# BluetoothAdapter1_0.net
KiCad netlist of a schematic drawn in Altium Designer
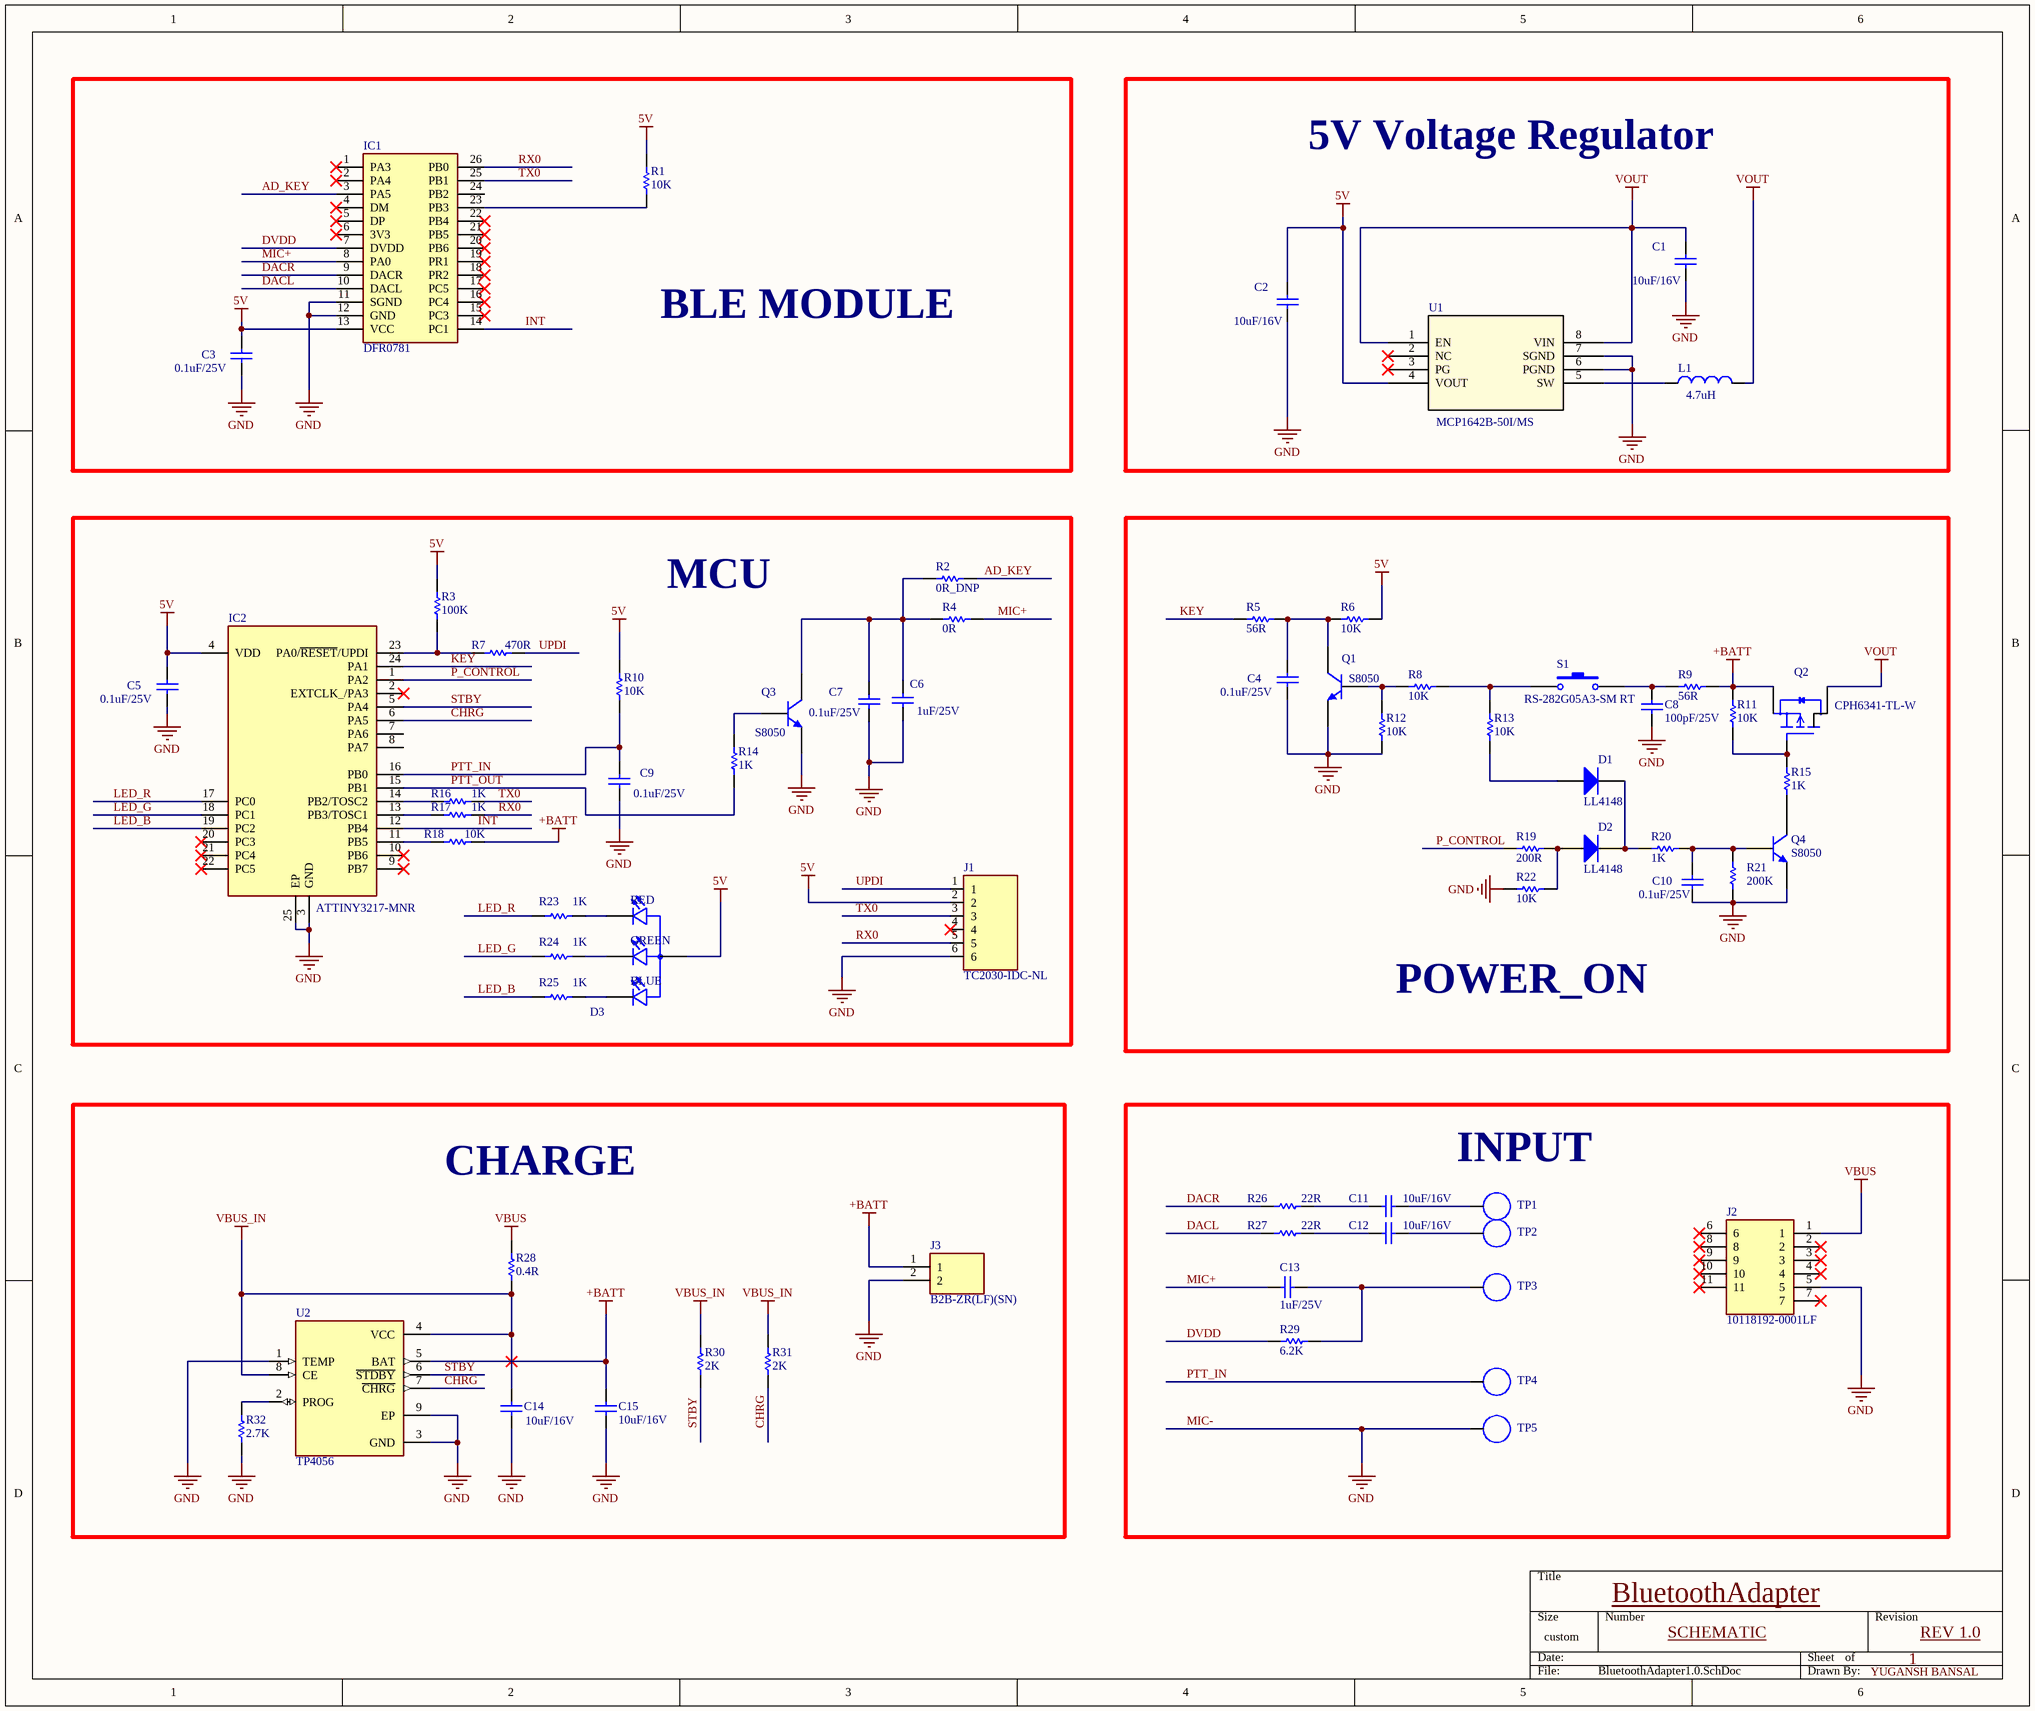
[diagram p0: BluetoothAdapter1.0.SchDoc]

(export (version "E")
  (design (tool "Eeschema 10.0.6"))
  (components
    (comp (ref "C1")
      (value "10uF/16V")
      (footprint "BluetoothAdapter:C0603S")
      (description "10 µF ±20% 16V Ceramic Capacitor X5R 0603 (1608 Metric)")
      (fields
        (field (name "MANUFACTURER") "Murata Electronics")
        (field (name "DIGI-KEY PART NUMBER") "490-10729-6-ND")
      )
      (libsource (lib "myLib") (part "Cap"))
    )
    (comp (ref "C2")
      (value "10uF/16V")
      (footprint "BluetoothAdapter:C0603S")
      (description "10 µF ±20% 16V Ceramic Capacitor X5R 0603 (1608 Metric)")
      (fields
        (field (name "MANUFACTURER") "Murata Electronics")
        (field (name "DIGI-KEY PART NUMBER") "490-10729-6-ND")
      )
      (libsource (lib "myLib") (part "Cap"))
    )
    (comp (ref "C3")
      (value "0.1uF/25V")
      (footprint "BluetoothAdapter:C0603S")
      (description "0.1 µF ±10% 25V Ceramic Capacitor X7R 0603 (1608 Metric)")
      (fields
        (field (name "MANUFACTURER") "KEMET")
        (field (name "DIGI-KEY PART NUMBER") "399-C0603C104K3RAC7867TR-ND")
      )
      (libsource (lib "myLib") (part "Cap"))
    )
    (comp (ref "C4")
      (value "0.1uF/25V")
      (footprint "BluetoothAdapter:C0603S")
      (description "0.1 µF ±10% 25V Ceramic Capacitor X7R 0603 (1608 Metric)")
      (fields
        (field (name "MANUFACTURER") "KEMET")
        (field (name "DIGI-KEY PART NUMBER") "399-C0603C104K3RAC7867TR-ND")
      )
      (libsource (lib "myLib") (part "Cap"))
    )
    (comp (ref "C5")
      (value "0.1uF/25V")
      (footprint "BluetoothAdapter:C0603S")
      (description "0.1 µF ±10% 25V Ceramic Capacitor X7R 0603 (1608 Metric)")
      (fields
        (field (name "MANUFACTURER") "KEMET")
        (field (name "DIGI-KEY PART NUMBER") "399-C0603C104K3RAC7867TR-ND")
      )
      (libsource (lib "myLib") (part "Cap"))
    )
    (comp (ref "C6")
      (value "1uF/25V")
      (footprint "BluetoothAdapter:C0603S")
      (description "1 µF ±10% 25V Ceramic Capacitor X7R 0603 (1608 Metric)")
      (fields
        (field (name "MANUFACTURER") "KEMET")
        (field (name "DIGI-KEY PART NUMBER") "399-C0603C105K3RAC7867DKR-ND")
      )
      (libsource (lib "myLib") (part "Cap"))
    )
    (comp (ref "C7")
      (value "0.1uF/25V")
      (footprint "BluetoothAdapter:C0603S")
      (description "0.1 µF ±10% 25V Ceramic Capacitor X7R 0603 (1608 Metric)")
      (fields
        (field (name "MANUFACTURER") "KEMET")
        (field (name "DIGI-KEY PART NUMBER") "399-C0603C104K3RAC7867TR-ND")
      )
      (libsource (lib "myLib") (part "Cap"))
    )
    (comp (ref "C8")
      (value "100pF/25V")
      (footprint "BluetoothAdapter:C0603S")
      (description "0.1 µF ±10% 25V Ceramic Capacitor X7R 0603 (1608 Metric)")
      (fields
        (field (name "MANUFACTURER") "KEMET")
        (field (name "DIGI-KEY PART NUMBER") "399-C0603C101K3RACAUTODKR-ND")
      )
      (libsource (lib "myLib") (part "Cap"))
    )
    (comp (ref "C9")
      (value "0.1uF/25V")
      (footprint "BluetoothAdapter:C0603S")
      (description "0.1 µF ±10% 25V Ceramic Capacitor X7R 0603 (1608 Metric)")
      (fields
        (field (name "MANUFACTURER") "KEMET")
        (field (name "DIGI-KEY PART NUMBER") "399-C0603C104K3RAC7867TR-ND")
      )
      (libsource (lib "myLib") (part "Cap"))
    )
    (comp (ref "C10")
      (value "0.1uF/25V")
      (footprint "BluetoothAdapter:C0603S")
      (description "0.1 µF ±10% 25V Ceramic Capacitor X7R 0603 (1608 Metric)")
      (fields
        (field (name "MANUFACTURER") "KEMET")
        (field (name "DIGI-KEY PART NUMBER") "399-C0603C104K3RAC7867TR-ND")
      )
      (libsource (lib "myLib") (part "Cap"))
    )
    (comp (ref "C11")
      (value "10uF/16V")
      (footprint "BluetoothAdapter:C0603S")
      (description "10 µF ±20% 16V Ceramic Capacitor X5R 0603 (1608 Metric)")
      (fields
        (field (name "MANUFACTURER") "Murata Electronics")
        (field (name "DIGI-KEY PART NUMBER") "490-10729-6-ND")
      )
      (libsource (lib "myLib") (part "Cap"))
    )
    (comp (ref "C12")
      (value "10uF/16V")
      (footprint "BluetoothAdapter:C0603S")
      (description "10 µF ±20% 16V Ceramic Capacitor X5R 0603 (1608 Metric)")
      (fields
        (field (name "MANUFACTURER") "Murata Electronics")
        (field (name "DIGI-KEY PART NUMBER") "490-10729-6-ND")
      )
      (libsource (lib "myLib") (part "Cap"))
    )
    (comp (ref "C13")
      (value "1uF/25V")
      (footprint "BluetoothAdapter:C0603S")
      (description "1 µF ±10% 25V Ceramic Capacitor X7R 0603 (1608 Metric)")
      (fields
        (field (name "MANUFACTURER") "KEMET")
        (field (name "DIGI-KEY PART NUMBER") "399-C0603C105K3RAC7867DKR-ND")
      )
      (libsource (lib "myLib") (part "Cap"))
    )
    (comp (ref "C14")
      (value "10uF/16V")
      (footprint "BluetoothAdapter:C0603S")
      (description "10 µF ±20% 16V Ceramic Capacitor X5R 0603 (1608 Metric)")
      (fields
        (field (name "MANUFACTURER") "Murata Electronics")
        (field (name "DIGI-KEY PART NUMBER") "490-10729-6-ND")
      )
      (libsource (lib "myLib") (part "Cap"))
    )
    (comp (ref "C15")
      (value "10uF/16V")
      (footprint "BluetoothAdapter:C0603S")
      (description "10 µF ±20% 16V Ceramic Capacitor X5R 0603 (1608 Metric)")
      (fields
        (field (name "MANUFACTURER") "Murata Electronics")
        (field (name "DIGI-KEY PART NUMBER") "490-10729-6-ND")
      )
      (libsource (lib "myLib") (part "Cap"))
    )
    (comp (ref "D1")
      (value "LL4148")
      (footprint "DIO_LL4148")
      (description "Diode Standard 100 V 200mA Surface Mount SOD-80")
      (fields (field (name "MANUFACTURER") "onsemi") (field (name "DIGI-KEY PART NUMBER") "LL4148FSCT-ND"))
      (libsource (lib "Miscellaneous Devices") (part "Diode"))
    )
    (comp (ref "D2")
      (value "LL4148")
      (footprint "DIO_LL4148")
      (description "Diode Standard 100 V 200mA Surface Mount SOD-80")
      (fields (field (name "MANUFACTURER") "onsemi") (field (name "DIGI-KEY PART NUMBER") "LL4148FSCT-ND"))
      (libsource (lib "Miscellaneous Devices") (part "Diode"))
    )
    (comp (ref "D3")
      (value "LED RGB MIXED WHITE ( 1.6(L)X1.6")
      (footprint "BluetoothAdapter:LED_B38G3RGB-10D0003H2U1930")
      (description "Red, Green, Blue (RGB) LED Indication - Discrete 2V Red, 3V Green, 3V Blue 0606 (1616 Metric)")
      (fields
        (field (name "MANUFACTURER") "Harvatek Corporation")
        (field (name "DIGI-KEY PART NUMBER") "3147-B38G3RGB-10D0003H2U1930DKR-ND")
      )
      (libsource (lib "BluetoothAdapter") (part "B38G3RGB-10D0003H2U1930"))
    )
    (comp (ref "IC1")
      (value "DFR0781")
      (footprint "BluetoothAdapter:DFR0781")
      (description "Bluetooth Bluetooth v5.0 Transceiver Module Antenna Not Included Surface Mount")
      (fields (field (name "MANUFACTURER") "DFRobot") (field (name "DIGI-KEY PART NUMBER") "1738-DFR0781-ND"))
      (libsource (lib "BluetoothAdapter") (part "DFR0781"))
    )
    (comp (ref "IC2")
      (value "ATTINY3217-MNR")
      (footprint "BluetoothAdapter:QFN50P400X400X90-25N-D")
      (fields
        (field (name "MANUFACTURER") "Microchip")
        (field (name "DIGI-KEY PART NUMBER") "ATTINY3217-MNRDKR-ND")
        (field (name "Comment") "IC MCU 8BIT 32KB FLASH 24VQFN")
      )
      (libsource (lib "BluetoothAdapter") (part "ATTINY3217-MNR"))
    )
    (comp (ref "J1")
      (value "TC2030-IDC-NL")
      (footprint "BluetoothAdapter:TAG_TC2030-IDC-NL")
      (description "6-PIN PLUG-OF-NAILS CABLE 6")
      (fields (field (name "MF") "Tag-Connect"))
      (libsource (lib "BluetoothAdapter") (part "TC2030-IDC-NL"))
    )
    (comp (ref "J2")
      (value "10118192-0001LF")
      (footprint "BluetoothAdapter:101181920001LF")
      (description "USB - micro B USB 2.0 Receptacle Connector 5 Position Surface Mount, Right Angle")
      (fields (field (name "MANUFACTURER") "Amphenol") (field (name "DIGI-KEY PART NUMBER") "609-4613-6-ND"))
      (libsource (lib "BluetoothAdapter") (part "10118192-0001LF"))
    )
    (comp (ref "J3")
      (value "B2B-ZR(LF)(SN)")
      (footprint "BluetoothAdapter:SHDR2W50P0X150_1X2_450X350X450P")
      (description "Connector Header Through Hole 2 position 0.059\" (1.50mm)")
      (fields
        (field (name "MANUFACTURER") "JST (JAPAN SOLDERLESS TERMINALS)")
        (field (name "DIGI-KEY PART NUMBER") "455-1657-ND")
      )
      (libsource (lib "BluetoothAdapter") (part "B2B-ZR(LF)(SN)"))
    )
    (comp (ref "L1")
      (value "4.7uH")
      (footprint "INDC2520X100N:INDC2520X100N")
      (description "4.7 µH Shielded Multilayer Inductor 1.3 A 120mOhm 1008 (2520 Metric)")
      (fields
        (field (name "MANUFACTURER") "Abracon LLC")
        (field (name "DIGI-KEY PART NUMBER") "535-12797-6-ND")
      )
      (libsource (lib "Blueguard") (part "AIML-1008HC-4R7M-T"))
    )
    (comp (ref "Q1")
      (value "S8050")
      (footprint "BluetoothAdapter:SOT23-3D")
      (description "Bipolar (BJT) Transistor NPN 25 V 500 mA 150MHz 300 mW Surface Mount SOT-23")
      (fields (field (name "MANUFACTURER") "MDD") (field (name "DIGI-KEY PART NUMBER") "3372-S8050TR-ND"))
      (libsource (lib "BluetoothAdapter") (part "S8050"))
    )
    (comp (ref "Q2")
      (value "CPH6341-TL-W")
      (footprint "BluetoothAdapter:SOT95P285X140-6N")
      (description "P-Channel 30 V 5A (Ta) 1.6W (Ta) Surface Mount 6-CPH")
      (fields
        (field (name "MANUFACTURER") "onsemi")
        (field (name "DIGI-KEY PART NUMBER") "CPH6341-TL-WOSDKR-ND")
      )
      (libsource (lib "BluetoothAdapter") (part "CPH6341-TL-W"))
    )
    (comp (ref "Q3")
      (value "S8050")
      (footprint "BluetoothAdapter:SOT23-3D")
      (description "Bipolar (BJT) Transistor NPN 25 V 500 mA 150MHz 300 mW Surface Mount SOT-23")
      (fields (field (name "MANUFACTURER") "MDD") (field (name "DIGI-KEY PART NUMBER") "3372-S8050TR-ND"))
      (libsource (lib "BluetoothAdapter") (part "S8050"))
    )
    (comp (ref "Q4")
      (value "S8050")
      (footprint "BluetoothAdapter:SOT23-3D")
      (description "Bipolar (BJT) Transistor NPN 25 V 500 mA 150MHz 300 mW Surface Mount SOT-23")
      (fields (field (name "MANUFACTURER") "MDD") (field (name "DIGI-KEY PART NUMBER") "3372-S8050TR-ND"))
      (libsource (lib "BluetoothAdapter") (part "S8050"))
    )
    (comp (ref "R1")
      (value "10K")
      (footprint "BluetoothAdapter:R0603S")
      (description "10 kOhms ±1% 0.1W, 1/10W Chip Resistor 0603 (1608 Metric) Moisture Resistant Thick Film")
      (fields (field (name "MANUFACTURER") "YAGEO") (field (name "DIGI-KEY PART NUMBER") "311-10.0KHRCT-ND"))
      (libsource (lib "dif") (part "R0603"))
    )
    (comp (ref "R2")
      (value "0R_DNP")
      (footprint "BluetoothAdapter:R0603S")
      (description "0Ohms ±1% 0.1W, 1/10W Chip Resistor 0603 (1608 Metric) Moisture Resistant Thick Film")
      (fields (field (name "MANUFACTURER") "YAGEO") (field (name "DIGI-KEY PART NUMBER") "311-0.0GRDKR-ND"))
      (libsource (lib "dif") (part "R0603"))
    )
    (comp (ref "R3")
      (value "100K")
      (footprint "BluetoothAdapter:R0603S")
      (description "100 kOhms ±1% 0.1W, 1/10W Chip Resistor 0603 (1608 Metric) Moisture Resistant Thick Film")
      (fields (field (name "MANUFACTURER") "YAGEO") (field (name "DIGI-KEY PART NUMBER") "311-100KHRDKR-ND"))
      (libsource (lib "dif") (part "R0603"))
    )
    (comp (ref "R4")
      (value "0R")
      (footprint "BluetoothAdapter:R0603S")
      (description "0Ohms ±1% 0.1W, 1/10W Chip Resistor 0603 (1608 Metric) Moisture Resistant Thick Film")
      (fields (field (name "MANUFACTURER") "YAGEO") (field (name "DIGI-KEY PART NUMBER") "311-0.0GRDKR-ND"))
      (libsource (lib "dif") (part "R0603"))
    )
    (comp (ref "R5")
      (value "56R")
      (footprint "BluetoothAdapter:R0603S")
      (description "1 kOhms ±1% 0.1W, 1/10W Chip Resistor 0603 (1608 Metric) Moisture Resistant Thick Film")
      (fields (field (name "MANUFACTURER") "YAGEO") (field (name "DIGI-KEY PART NUMBER") "311-56.0HRDKR-ND"))
      (libsource (lib "dif") (part "R0603"))
    )
    (comp (ref "R6")
      (value "10K")
      (footprint "BluetoothAdapter:R0603S")
      (description "10 kOhms ±1% 0.1W, 1/10W Chip Resistor 0603 (1608 Metric) Moisture Resistant Thick Film")
      (fields (field (name "MANUFACTURER") "YAGEO") (field (name "DIGI-KEY PART NUMBER") "311-10.0KHRCT-ND"))
      (libsource (lib "dif") (part "R0603"))
    )
    (comp (ref "R7")
      (value "470R")
      (footprint "BluetoothAdapter:R0603S")
      (description "470 Ohms ±1% 0.1W, 1/10W Chip Resistor 0603 (1608 Metric) Moisture Resistant Thick Film")
      (fields (field (name "MANUFACTURER") "YAGEO") (field (name "DIGI-KEY PART NUMBER") "311-470HRDKR-ND"))
      (libsource (lib "dif") (part "R0603"))
    )
    (comp (ref "R8")
      (value "10K")
      (footprint "BluetoothAdapter:R0603S")
      (description "10 kOhms ±1% 0.1W, 1/10W Chip Resistor 0603 (1608 Metric) Moisture Resistant Thick Film")
      (fields (field (name "MANUFACTURER") "YAGEO") (field (name "DIGI-KEY PART NUMBER") "311-10.0KHRCT-ND"))
      (libsource (lib "dif") (part "R0603"))
    )
    (comp (ref "R9")
      (value "56R")
      (footprint "BluetoothAdapter:R0603S")
      (description "1 kOhms ±1% 0.1W, 1/10W Chip Resistor 0603 (1608 Metric) Moisture Resistant Thick Film")
      (fields (field (name "MANUFACTURER") "YAGEO") (field (name "DIGI-KEY PART NUMBER") "311-56.0HRDKR-ND"))
      (libsource (lib "dif") (part "R0603"))
    )
    (comp (ref "R10")
      (value "10K")
      (footprint "BluetoothAdapter:R0603S")
      (description "10 kOhms ±1% 0.1W, 1/10W Chip Resistor 0603 (1608 Metric) Moisture Resistant Thick Film")
      (fields (field (name "MANUFACTURER") "YAGEO") (field (name "DIGI-KEY PART NUMBER") "311-10.0KHRCT-ND"))
      (libsource (lib "dif") (part "R0603"))
    )
    (comp (ref "R11")
      (value "10K")
      (footprint "BluetoothAdapter:R0603S")
      (description "10 kOhms ±1% 0.1W, 1/10W Chip Resistor 0603 (1608 Metric) Moisture Resistant Thick Film")
      (fields (field (name "MANUFACTURER") "YAGEO") (field (name "DIGI-KEY PART NUMBER") "311-10.0KHRCT-ND"))
      (libsource (lib "dif") (part "R0603"))
    )
    (comp (ref "R12")
      (value "10K")
      (footprint "BluetoothAdapter:R0603S")
      (description "10 kOhms ±1% 0.1W, 1/10W Chip Resistor 0603 (1608 Metric) Moisture Resistant Thick Film")
      (fields (field (name "MANUFACTURER") "YAGEO") (field (name "DIGI-KEY PART NUMBER") "311-10.0KHRCT-ND"))
      (libsource (lib "dif") (part "R0603"))
    )
    (comp (ref "R13")
      (value "10K")
      (footprint "BluetoothAdapter:R0603S")
      (description "10 kOhms ±1% 0.1W, 1/10W Chip Resistor 0603 (1608 Metric) Moisture Resistant Thick Film")
      (fields (field (name "MANUFACTURER") "YAGEO") (field (name "DIGI-KEY PART NUMBER") "311-10.0KHRCT-ND"))
      (libsource (lib "dif") (part "R0603"))
    )
    (comp (ref "R14")
      (value "1K")
      (footprint "BluetoothAdapter:R0603S")
      (description "1 kOhms ±1% 0.1W, 1/10W Chip Resistor 0603 (1608 Metric) Moisture Resistant Thick Film")
      (fields (field (name "MANUFACTURER") "YAGEO") (field (name "DIGI-KEY PART NUMBER") "311-1.00KHRTR-ND"))
      (libsource (lib "dif") (part "R0603"))
    )
    (comp (ref "R15")
      (value "1K")
      (footprint "BluetoothAdapter:R0603S")
      (description "1 kOhms ±1% 0.1W, 1/10W Chip Resistor 0603 (1608 Metric) Moisture Resistant Thick Film")
      (fields (field (name "MANUFACTURER") "YAGEO") (field (name "DIGI-KEY PART NUMBER") "311-1.00KHRTR-ND"))
      (libsource (lib "dif") (part "R0603"))
    )
    (comp (ref "R16")
      (value "1K")
      (footprint "BluetoothAdapter:R0603S")
      (description "1 kOhms ±1% 0.1W, 1/10W Chip Resistor 0603 (1608 Metric) Moisture Resistant Thick Film")
      (fields (field (name "MANUFACTURER") "YAGEO") (field (name "DIGI-KEY PART NUMBER") "311-1.00KHRTR-ND"))
      (libsource (lib "dif") (part "R0603"))
    )
    (comp (ref "R17")
      (value "1K")
      (footprint "BluetoothAdapter:R0603S")
      (description "1 kOhms ±1% 0.1W, 1/10W Chip Resistor 0603 (1608 Metric) Moisture Resistant Thick Film")
      (fields (field (name "MANUFACTURER") "YAGEO") (field (name "DIGI-KEY PART NUMBER") "311-1.00KHRTR-ND"))
      (libsource (lib "dif") (part "R0603"))
    )
    (comp (ref "R18")
      (value "10K")
      (footprint "BluetoothAdapter:R0603S")
      (description "10 kOhms ±1% 0.1W, 1/10W Chip Resistor 0603 (1608 Metric) Moisture Resistant Thick Film")
      (fields (field (name "MANUFACTURER") "YAGEO") (field (name "DIGI-KEY PART NUMBER") "311-10.0KHRCT-ND"))
      (libsource (lib "dif") (part "R0603"))
    )
    (comp (ref "R19")
      (value "200R")
      (footprint "BluetoothAdapter:R0603S")
      (description "10 kOhms ±1% 0.1W, 1/10W Chip Resistor 0603 (1608 Metric) Moisture Resistant Thick Film")
      (fields (field (name "MANUFACTURER") "YAGEO") (field (name "DIGI-KEY PART NUMBER") "311-200HRDKR-ND"))
      (libsource (lib "dif") (part "R0603"))
    )
    (comp (ref "R20")
      (value "1K")
      (footprint "BluetoothAdapter:R0603S")
      (description "1 kOhms ±1% 0.1W, 1/10W Chip Resistor 0603 (1608 Metric) Moisture Resistant Thick Film")
      (fields (field (name "MANUFACTURER") "YAGEO") (field (name "DIGI-KEY PART NUMBER") "311-1.00KHRTR-ND"))
      (libsource (lib "dif") (part "R0603"))
    )
    (comp (ref "R21")
      (value "200K")
      (footprint "BluetoothAdapter:R0603S")
      (description "100 kOhms ±1% 0.1W, 1/10W Chip Resistor 0603 (1608 Metric) Moisture Resistant Thick Film")
      (fields
        (field (name "MANUFACTURER") "YAGEO")
        (field (name "DIGI-KEY PART NUMBER") "13-RC0603FR-10200KLDKR-ND")
      )
      (libsource (lib "dif") (part "R0603"))
    )
    (comp (ref "R22")
      (value "10K")
      (footprint "BluetoothAdapter:R0603S")
      (description "10 kOhms ±1% 0.1W, 1/10W Chip Resistor 0603 (1608 Metric) Moisture Resistant Thick Film")
      (fields (field (name "MANUFACTURER") "YAGEO") (field (name "DIGI-KEY PART NUMBER") "311-10.0KHRCT-ND"))
      (libsource (lib "dif") (part "R0603"))
    )
    (comp (ref "R23")
      (value "1K")
      (footprint "BluetoothAdapter:R0603S")
      (description "1 kOhms ±1% 0.1W, 1/10W Chip Resistor 0603 (1608 Metric) Moisture Resistant Thick Film")
      (fields (field (name "MANUFACTURER") "YAGEO") (field (name "DIGI-KEY PART NUMBER") "311-1.00KHRTR-ND"))
      (libsource (lib "dif") (part "R0603"))
    )
    (comp (ref "R24")
      (value "1K")
      (footprint "BluetoothAdapter:R0603S")
      (description "1 kOhms ±1% 0.1W, 1/10W Chip Resistor 0603 (1608 Metric) Moisture Resistant Thick Film")
      (fields (field (name "MANUFACTURER") "YAGEO") (field (name "DIGI-KEY PART NUMBER") "311-1.00KHRTR-ND"))
      (libsource (lib "dif") (part "R0603"))
    )
    (comp (ref "R25")
      (value "1K")
      (footprint "BluetoothAdapter:R0603S")
      (description "1 kOhms ±1% 0.1W, 1/10W Chip Resistor 0603 (1608 Metric) Moisture Resistant Thick Film")
      (fields (field (name "MANUFACTURER") "YAGEO") (field (name "DIGI-KEY PART NUMBER") "311-1.00KHRTR-ND"))
      (libsource (lib "dif") (part "R0603"))
    )
    (comp (ref "R26")
      (value "22R")
      (footprint "BluetoothAdapter:R0603S")
      (description "22 Ohms ±5% 0.1W, 1/10W Chip Resistor 0603 (1608 Metric) Moisture Resistant Thick Film")
      (fields (field (name "MANUFACTURER") "YAGEO") (field (name "DIGI-KEY PART NUMBER") "311-22GRDKR-ND"))
      (libsource (lib "dif") (part "R0603"))
    )
    (comp (ref "R27")
      (value "22R")
      (footprint "BluetoothAdapter:R0603S")
      (description "22 Ohms ±5% 0.1W, 1/10W Chip Resistor 0603 (1608 Metric) Moisture Resistant Thick Film")
      (fields (field (name "MANUFACTURER") "YAGEO") (field (name "DIGI-KEY PART NUMBER") "311-22GRDKR-ND"))
      (libsource (lib "dif") (part "R0603"))
    )
    (comp (ref "R28")
      (value "0.4R")
      (footprint "BluetoothAdapter:R1206S")
      (fields
        (field (name "MANUFACTURER") "YAGEO")
        (field (name "DIGI-KEY PART NUMBER") "311-.4LWDKR-ND")
        (field (name "Comment") "RES 0.4 OHM 1% 1/4W 1206")
      )
      (libsource (lib "dif") (part "R0603"))
    )
    (comp (ref "R29")
      (value "6.2K")
      (footprint "BluetoothAdapter:R0603S")
      (description "6.2 kOhms ±1% 0.1W, 1/10W Chip Resistor 0603 (1608 Metric) Moisture Resistant Thick Film")
      (fields (field (name "MANUFACTURER") "YAGEO") (field (name "DIGI-KEY PART NUMBER") "311-6.20KHRDKR-ND"))
      (libsource (lib "dif") (part "R0603"))
    )
    (comp (ref "R30")
      (value "2K")
      (footprint "BluetoothAdapter:R0603S")
      (description "2 kOhms ±1% 0.1W, 1/10W Chip Resistor 0603 (1608 Metric) Moisture Resistant Thick Film")
      (fields (field (name "MANUFACTURER") "YAGEO") (field (name "DIGI-KEY PART NUMBER") "311-2.00KHRDKR-ND"))
      (libsource (lib "dif") (part "R0603"))
    )
    (comp (ref "R31")
      (value "2K")
      (footprint "BluetoothAdapter:R0603S")
      (description "2 kOhms ±1% 0.1W, 1/10W Chip Resistor 0603 (1608 Metric) Moisture Resistant Thick Film")
      (fields (field (name "MANUFACTURER") "YAGEO") (field (name "DIGI-KEY PART NUMBER") "311-2.00KHRDKR-ND"))
      (libsource (lib "dif") (part "R0603"))
    )
    (comp (ref "R32")
      (value "2.7K")
      (footprint "BluetoothAdapter:R0603S")
      (description "2.7 kOhms ±1% 0.1W, 1/10W Chip Resistor 0603 (1608 Metric) Moisture Resistant Thick Film")
      (fields (field (name "MANUFACTURER") "YAGEO") (field (name "DIGI-KEY PART NUMBER") "311-2.70KHRDKR-ND"))
      (libsource (lib "dif") (part "R0603"))
    )
    (comp (ref "S1")
      (value "RS-282G05A3-SM RT")
      (footprint "BluetoothAdapter:RS282G05A3SMRT")
      (description "Tactile Switch SPST-NO Top Actuated Surface Mount")
      (fields
        (field (name "MANUFACTURER") "C & K COMPONENTS")
        (field (name "DIGI-KEY PART NUMBER") "CKN10384DKR-ND")
      )
      (libsource (lib "BluetoothAdapter") (part "RS282G05A3SMRT"))
    )
    (comp (ref "TP1")
      (value "TP")
      (footprint "BluetoothAdapter:TP")
      (libsource (lib "BluetoothAdapter") (part "TP"))
    )
    (comp (ref "TP2")
      (value "TP")
      (footprint "BluetoothAdapter:TP")
      (libsource (lib "BluetoothAdapter") (part "TP"))
    )
    (comp (ref "TP3")
      (value "TP")
      (footprint "BluetoothAdapter:TP")
      (libsource (lib "BluetoothAdapter") (part "TP"))
    )
    (comp (ref "TP4")
      (value "TP")
      (footprint "BluetoothAdapter:TP")
      (libsource (lib "BluetoothAdapter") (part "TP"))
    )
    (comp (ref "TP5")
      (value "TP")
      (footprint "BluetoothAdapter:TP")
      (libsource (lib "BluetoothAdapter") (part "TP"))
    )
    (comp (ref "U1")
      (value "MCP1642B-50I/MS")
      (footprint "MCP1642B-50:MCP1642B-50I/MS")
      (fields
        (field (name "MANUFACTURER") "Microchip Technology")
        (field (name "DIGI-KEY PART NUMBER") "MCP1642B-50I/MS-ND")
        (field (name "Comment") "IC REG BOOST 5V 800MA 8MSOP")
      )
      (libsource (lib "Blueguard") (part "MCP1642B-50I/MS"))
    )
    (comp (ref "U2")
      (value "TP4056")
      (footprint "BluetoothAdapter:SOP127P600X175-9N")
      (description "Complete single cell Li-Ion battery with a constant current / constant voltage linear charger")
      (fields
        (field (name "MANUFACTURER") "TPOWER semiconductor Co.,LTD.")
        (field (name "DIGI-KEY PART NUMBER") "C382139")
      )
      (libsource (lib "BluetoothAdapter") (part "TP4056"))
    )
  )
  (nets
    (net (code "1") (name "+BATT") (class "Default")
      (node (ref "C15") (pin "2") (pinfunction "2_2") (pintype "passive"))
      (node (ref "J3") (pin "1") (pinfunction "1_1") (pintype "passive"))
      (node (ref "Q2") (pin "4") (pinfunction "S_4") (pintype "passive"))
      (node (ref "R11") (pin "1") (pinfunction "1_1") (pintype "passive"))
      (node (ref "R18") (pin "2") (pinfunction "2_2") (pintype "passive"))
      (node (ref "R9") (pin "2") (pinfunction "2_2") (pintype "passive"))
      (node (ref "U2") (pin "5") (pinfunction "BAT_5") (pintype "output"))
    )
    (net (code "2") (name "/AD_KEY") (class "Default")
      (node (ref "IC1") (pin "3") (pinfunction "PA5_3") (pintype "passive"))
      (node (ref "R2") (pin "1") (pinfunction "1_1") (pintype "passive"))
    )
    (net (code "3") (name "/CHRG") (class "Default")
      (node (ref "IC2") (pin "6") (pinfunction "PA5_6") (pintype "passive"))
      (node (ref "R31") (pin "2") (pinfunction "2_2") (pintype "passive"))
      (node (ref "U2") (pin "7") (pinfunction "~{CHRG}_7") (pintype "output"))
    )
    (net (code "4") (name "/DACL") (class "Default")
      (node (ref "IC1") (pin "10") (pinfunction "DACL_10") (pintype "passive"))
      (node (ref "R27") (pin "1") (pinfunction "1_1") (pintype "passive"))
    )
    (net (code "5") (name "/DACR") (class "Default")
      (node (ref "IC1") (pin "9") (pinfunction "DACR_9") (pintype "passive"))
      (node (ref "R26") (pin "1") (pinfunction "1_1") (pintype "passive"))
    )
    (net (code "6") (name "/DVDD") (class "Default")
      (node (ref "IC1") (pin "7") (pinfunction "DVDD_7") (pintype "passive"))
      (node (ref "R29") (pin "1") (pinfunction "1_1") (pintype "passive"))
    )
    (net (code "7") (name "/INT") (class "Default")
      (node (ref "IC1") (pin "14") (pinfunction "PC1_14") (pintype "passive"))
      (node (ref "IC2") (pin "12") (pinfunction "PB4_12") (pintype "passive"))
    )
    (net (code "8") (name "/KEY") (class "Default")
      (node (ref "IC2") (pin "24") (pinfunction "PA1_24") (pintype "passive"))
      (node (ref "R5") (pin "1") (pinfunction "1_1") (pintype "passive"))
    )
    (net (code "9") (name "/LED_B") (class "Default")
      (node (ref "IC2") (pin "19") (pinfunction "PC2_19") (pintype "passive"))
      (node (ref "R25") (pin "1") (pinfunction "1_1") (pintype "passive"))
    )
    (net (code "10") (name "/LED_G") (class "Default")
      (node (ref "IC2") (pin "18") (pinfunction "PC1_18") (pintype "passive"))
      (node (ref "R24") (pin "1") (pinfunction "1_1") (pintype "passive"))
    )
    (net (code "11") (name "/LED_R") (class "Default")
      (node (ref "IC2") (pin "17") (pinfunction "PC0_17") (pintype "passive"))
      (node (ref "R23") (pin "1") (pinfunction "1_1") (pintype "passive"))
    )
    (net (code "12") (name "/MIC+") (class "Default")
      (node (ref "C13") (pin "1") (pinfunction "1_1") (pintype "passive"))
      (node (ref "IC1") (pin "8") (pinfunction "PA0_8") (pintype "passive"))
      (node (ref "R4") (pin "2") (pinfunction "2_2") (pintype "passive"))
    )
    (net (code "13") (name "/PTT_IN") (class "Default")
      (node (ref "C9") (pin "1") (pinfunction "1_1") (pintype "passive"))
      (node (ref "IC2") (pin "16") (pinfunction "PB0_16") (pintype "passive"))
      (node (ref "R10") (pin "2") (pinfunction "2_2") (pintype "passive"))
      (node (ref "TP4") (pin "1") (pinfunction "1_1") (pintype "passive"))
    )
    (net (code "14") (name "/PTT_OUT") (class "Default")
      (node (ref "IC2") (pin "15") (pinfunction "PB1_15") (pintype "passive"))
      (node (ref "R14") (pin "1") (pinfunction "1_1") (pintype "passive"))
    )
    (net (code "15") (name "/P_CONTROL") (class "Default")
      (node (ref "IC2") (pin "1") (pinfunction "PA2_1") (pintype "passive"))
      (node (ref "R19") (pin "1") (pinfunction "1_1") (pintype "passive"))
    )
    (net (code "16") (name "/RX0") (class "Default")
      (node (ref "IC1") (pin "26") (pinfunction "PB0_26") (pintype "passive"))
      (node (ref "J1") (pin "5") (pinfunction "5_5") (pintype "passive"))
      (node (ref "R17") (pin "2") (pinfunction "2_2") (pintype "passive"))
    )
    (net (code "17") (name "/STBY") (class "Default")
      (node (ref "IC2") (pin "5") (pinfunction "PA4_5") (pintype "passive"))
      (node (ref "R30") (pin "2") (pinfunction "2_2") (pintype "passive"))
      (node (ref "U2") (pin "6") (pinfunction "~{STDBY}_6") (pintype "output"))
    )
    (net (code "18") (name "/TX0") (class "Default")
      (node (ref "IC1") (pin "25") (pinfunction "PB1_25") (pintype "passive"))
      (node (ref "J1") (pin "3") (pinfunction "3_3") (pintype "passive"))
      (node (ref "R16") (pin "2") (pinfunction "2_2") (pintype "passive"))
    )
    (net (code "19") (name "/UPDI") (class "Default")
      (node (ref "J1") (pin "1") (pinfunction "1_1") (pintype "passive"))
      (node (ref "R7") (pin "1") (pinfunction "1_1") (pintype "passive"))
    )
    (net (code "20") (name "5V") (class "Default")
      (node (ref "C2") (pin "2") (pinfunction "2_2") (pintype "passive"))
      (node (ref "C3") (pin "1") (pinfunction "1_1") (pintype "passive"))
      (node (ref "C5") (pin "1") (pinfunction "1_1") (pintype "passive"))
      (node (ref "D3") (pin "3") (pinfunction "A_3") (pintype "passive"))
      (node (ref "IC1") (pin "13") (pinfunction "VCC_13") (pintype "passive"))
      (node (ref "IC2") (pin "4") (pinfunction "VDD_4") (pintype "passive"))
      (node (ref "J1") (pin "2") (pinfunction "2_2") (pintype "passive"))
      (node (ref "R1") (pin "2") (pinfunction "2_2") (pintype "passive"))
      (node (ref "R10") (pin "1") (pinfunction "1_1") (pintype "passive"))
      (node (ref "R3") (pin "1") (pinfunction "1_1") (pintype "passive"))
      (node (ref "R6") (pin "1") (pinfunction "1_1") (pintype "passive"))
      (node (ref "U1") (pin "4") (pinfunction "VOUT_4") (pintype "passive"))
    )
    (net (code "21") (name "GND") (class "Default")
      (node (ref "C1") (pin "1") (pinfunction "1_1") (pintype "passive"))
      (node (ref "C10") (pin "2") (pinfunction "2_2") (pintype "passive"))
      (node (ref "C14") (pin "1") (pinfunction "1_1") (pintype "passive"))
      (node (ref "C15") (pin "1") (pinfunction "1_1") (pintype "passive"))
      (node (ref "C2") (pin "1") (pinfunction "1_1") (pintype "passive"))
      (node (ref "C3") (pin "2") (pinfunction "2_2") (pintype "passive"))
      (node (ref "C4") (pin "2") (pinfunction "2_2") (pintype "passive"))
      (node (ref "C5") (pin "2") (pinfunction "2_2") (pintype "passive"))
      (node (ref "C6") (pin "2") (pinfunction "2_2") (pintype "passive"))
      (node (ref "C7") (pin "2") (pinfunction "2_2") (pintype "passive"))
      (node (ref "C8") (pin "1") (pinfunction "1_1") (pintype "passive"))
      (node (ref "C9") (pin "2") (pinfunction "2_2") (pintype "passive"))
      (node (ref "IC1") (pin "11") (pinfunction "SGND_11") (pintype "passive"))
      (node (ref "IC1") (pin "12") (pinfunction "GND_12") (pintype "passive"))
      (node (ref "IC2") (pin "25") (pinfunction "EP_25") (pintype "passive"))
      (node (ref "IC2") (pin "3") (pinfunction "GND_3") (pintype "passive"))
      (node (ref "J1") (pin "6") (pinfunction "6_6") (pintype "passive"))
      (node (ref "J2") (pin "5") (pinfunction "5_5") (pintype "passive"))
      (node (ref "J3") (pin "2") (pinfunction "2_2") (pintype "passive"))
      (node (ref "Q1") (pin "3") (pinfunction "E_3") (pintype "passive"))
      (node (ref "Q3") (pin "3") (pinfunction "E_3") (pintype "passive"))
      (node (ref "Q4") (pin "3") (pinfunction "E_3") (pintype "passive"))
      (node (ref "R12") (pin "2") (pinfunction "2_2") (pintype "passive"))
      (node (ref "R21") (pin "1") (pinfunction "1_1") (pintype "passive"))
      (node (ref "R22") (pin "1") (pinfunction "1_1") (pintype "passive"))
      (node (ref "R32") (pin "2") (pinfunction "2_2") (pintype "passive"))
      (node (ref "TP5") (pin "1") (pinfunction "1_1") (pintype "passive"))
      (node (ref "U1") (pin "6") (pinfunction "PGND_6") (pintype "passive"))
      (node (ref "U1") (pin "7") (pinfunction "SGND_7") (pintype "passive"))
      (node (ref "U2") (pin "1") (pinfunction "TEMP_1") (pintype "input"))
      (node (ref "U2") (pin "3") (pinfunction "GND_3") (pintype "power_in"))
      (node (ref "U2") (pin "9") (pinfunction "EP_9") (pintype "passive"))
    )
    (net (code "22") (name "Net-(C8-Pad2)") (class "Default")
      (node (ref "C8") (pin "2") (pinfunction "2_2") (pintype "passive"))
      (node (ref "R9") (pin "1") (pinfunction "1_1") (pintype "passive"))
      (node (ref "S1") (pin "2") (pinfunction "2_2") (pintype "passive"))
    )
    (net (code "23") (name "Net-(C11-Pad1)") (class "Default")
      (node (ref "C11") (pin "1") (pinfunction "1_1") (pintype "passive"))
      (node (ref "TP1") (pin "1") (pinfunction "1_1") (pintype "passive"))
    )
    (net (code "24") (name "Net-(C11-Pad2)") (class "Default")
      (node (ref "C11") (pin "2") (pinfunction "2_2") (pintype "passive"))
      (node (ref "R26") (pin "2") (pinfunction "2_2") (pintype "passive"))
    )
    (net (code "25") (name "Net-(C12-Pad1)") (class "Default")
      (node (ref "C12") (pin "1") (pinfunction "1_1") (pintype "passive"))
      (node (ref "TP2") (pin "1") (pinfunction "1_1") (pintype "passive"))
    )
    (net (code "26") (name "Net-(C12-Pad2)") (class "Default")
      (node (ref "C12") (pin "2") (pinfunction "2_2") (pintype "passive"))
      (node (ref "R27") (pin "2") (pinfunction "2_2") (pintype "passive"))
    )
    (net (code "27") (name "Net-(C13-Pad2)") (class "Default")
      (node (ref "C13") (pin "2") (pinfunction "2_2") (pintype "passive"))
      (node (ref "R29") (pin "2") (pinfunction "2_2") (pintype "passive"))
      (node (ref "TP3") (pin "1") (pinfunction "1_1") (pintype "passive"))
    )
    (net (code "28") (name "Net-(D1-A)") (class "Default")
      (node (ref "D1") (pin "1") (pinfunction "A_1") (pintype "passive"))
      (node (ref "R13") (pin "2") (pinfunction "2_2") (pintype "passive"))
    )
    (net (code "29") (name "Net-(D1-K)") (class "Default")
      (node (ref "D1") (pin "2") (pinfunction "K_2") (pintype "passive"))
      (node (ref "D2") (pin "2") (pinfunction "K_2") (pintype "passive"))
      (node (ref "R20") (pin "2") (pinfunction "2_2") (pintype "passive"))
    )
    (net (code "30") (name "Net-(D2-A)") (class "Default")
      (node (ref "D2") (pin "1") (pinfunction "A_1") (pintype "passive"))
      (node (ref "R19") (pin "2") (pinfunction "2_2") (pintype "passive"))
      (node (ref "R22") (pin "2") (pinfunction "2_2") (pintype "passive"))
    )
    (net (code "31") (name "Net-(D3-B_C)") (class "Default")
      (node (ref "D3") (pin "2") (pinfunction "B_C_2") (pintype "passive"))
      (node (ref "R25") (pin "2") (pinfunction "2_2") (pintype "passive"))
    )
    (net (code "32") (name "Net-(D3-G_C)") (class "Default")
      (node (ref "D3") (pin "1") (pinfunction "G_C_1") (pintype "passive"))
      (node (ref "R24") (pin "2") (pinfunction "2_2") (pintype "passive"))
    )
    (net (code "33") (name "Net-(D3-R_C)") (class "Default")
      (node (ref "D3") (pin "4") (pinfunction "R_C_4") (pintype "passive"))
      (node (ref "R23") (pin "2") (pinfunction "2_2") (pintype "passive"))
    )
    (net (code "34") (name "Net-(IC1-PB3)") (class "Default")
      (node (ref "IC1") (pin "23") (pinfunction "PB3_23") (pintype "passive"))
      (node (ref "R1") (pin "1") (pinfunction "1_1") (pintype "passive"))
    )
    (net (code "35") (name "Net-(IC2-PA0{slash}~{RESET}{slash}UPDI)") (class "Default")
      (node (ref "IC2") (pin "23") (pinfunction "PA0/~{RESET}/UPDI_23") (pintype "passive"))
      (node (ref "R3") (pin "2") (pinfunction "2_2") (pintype "passive"))
      (node (ref "R7") (pin "2") (pinfunction "2_2") (pintype "passive"))
    )
    (net (code "36") (name "Net-(IC2-PB2{slash}TOSC2)") (class "Default")
      (node (ref "IC2") (pin "14") (pinfunction "PB2/TOSC2_14") (pintype "passive"))
      (node (ref "R16") (pin "1") (pinfunction "1_1") (pintype "passive"))
    )
    (net (code "37") (name "Net-(IC2-PB3{slash}TOSC1)") (class "Default")
      (node (ref "IC2") (pin "13") (pinfunction "PB3/TOSC1_13") (pintype "passive"))
      (node (ref "R17") (pin "1") (pinfunction "1_1") (pintype "passive"))
    )
    (net (code "38") (name "Net-(IC2-PB5)") (class "Default")
      (node (ref "IC2") (pin "11") (pinfunction "PB5_11") (pintype "passive"))
      (node (ref "R18") (pin "1") (pinfunction "1_1") (pintype "passive"))
    )
    (net (code "39") (name "Net-(Q1-B)") (class "Default")
      (node (ref "Q1") (pin "1") (pinfunction "B_1") (pintype "passive"))
      (node (ref "R12") (pin "1") (pinfunction "1_1") (pintype "passive"))
      (node (ref "R8") (pin "2") (pinfunction "2_2") (pintype "passive"))
    )
    (net (code "40") (name "Net-(Q1-C)") (class "Default")
      (node (ref "C4") (pin "1") (pinfunction "1_1") (pintype "passive"))
      (node (ref "Q1") (pin "2") (pinfunction "C_2") (pintype "passive"))
      (node (ref "R5") (pin "2") (pinfunction "2_2") (pintype "passive"))
      (node (ref "R6") (pin "2") (pinfunction "2_2") (pintype "passive"))
    )
    (net (code "41") (name "Net-(Q2-G)") (class "Default")
      (node (ref "Q2") (pin "3") (pinfunction "G_3") (pintype "passive"))
      (node (ref "R11") (pin "2") (pinfunction "2_2") (pintype "passive"))
      (node (ref "R15") (pin "1") (pinfunction "1_1") (pintype "passive"))
    )
    (net (code "42") (name "Net-(Q3-B)") (class "Default")
      (node (ref "Q3") (pin "1") (pinfunction "B_1") (pintype "passive"))
      (node (ref "R14") (pin "2") (pinfunction "2_2") (pintype "passive"))
    )
    (net (code "43") (name "Net-(Q3-C)") (class "Default")
      (node (ref "C6") (pin "1") (pinfunction "1_1") (pintype "passive"))
      (node (ref "C7") (pin "1") (pinfunction "1_1") (pintype "passive"))
      (node (ref "Q3") (pin "2") (pinfunction "C_2") (pintype "passive"))
      (node (ref "R2") (pin "2") (pinfunction "2_2") (pintype "passive"))
      (node (ref "R4") (pin "1") (pinfunction "1_1") (pintype "passive"))
    )
    (net (code "44") (name "Net-(Q4-B)") (class "Default")
      (node (ref "C10") (pin "1") (pinfunction "1_1") (pintype "passive"))
      (node (ref "Q4") (pin "1") (pinfunction "B_1") (pintype "passive"))
      (node (ref "R20") (pin "1") (pinfunction "1_1") (pintype "passive"))
      (node (ref "R21") (pin "2") (pinfunction "2_2") (pintype "passive"))
    )
    (net (code "45") (name "Net-(Q4-C)") (class "Default")
      (node (ref "Q4") (pin "2") (pinfunction "C_2") (pintype "passive"))
      (node (ref "R15") (pin "2") (pinfunction "2_2") (pintype "passive"))
    )
    (net (code "46") (name "Net-(R13-Pad1)") (class "Default")
      (node (ref "R13") (pin "1") (pinfunction "1_1") (pintype "passive"))
      (node (ref "R8") (pin "1") (pinfunction "1_1") (pintype "passive"))
      (node (ref "S1") (pin "1") (pinfunction "1_1") (pintype "passive"))
    )
    (net (code "47") (name "Net-(U1-SW)") (class "Default")
      (node (ref "L1") (pin "1") (pinfunction "1_1") (pintype "passive"))
      (node (ref "U1") (pin "5") (pinfunction "SW_5") (pintype "passive"))
    )
    (net (code "48") (name "Net-(U2-PROG)") (class "Default")
      (node (ref "R32") (pin "1") (pinfunction "1_1") (pintype "passive"))
      (node (ref "U2") (pin "2") (pinfunction "PROG_2") (pintype "bidirectional"))
    )
    (net (code "49") (name "VBUS") (class "Default")
      (node (ref "J2") (pin "1") (pinfunction "1_1") (pintype "passive"))
      (node (ref "R28") (pin "1") (pinfunction "1_1") (pintype "passive"))
    )
    (net (code "50") (name "VBUS_IN") (class "Default")
      (node (ref "C14") (pin "2") (pinfunction "2_2") (pintype "passive"))
      (node (ref "R28") (pin "2") (pinfunction "2_2") (pintype "passive"))
      (node (ref "R30") (pin "1") (pinfunction "1_1") (pintype "passive"))
      (node (ref "R31") (pin "1") (pinfunction "1_1") (pintype "passive"))
      (node (ref "U2") (pin "4") (pinfunction "VCC_4") (pintype "power_in"))
      (node (ref "U2") (pin "8") (pinfunction "CE_8") (pintype "input"))
    )
    (net (code "51") (name "VOUT") (class "Default")
      (node (ref "C1") (pin "2") (pinfunction "2_2") (pintype "passive"))
      (node (ref "L1") (pin "2") (pinfunction "2_2") (pintype "passive"))
      (node (ref "Q2") (pin "6") (pinfunction "D@4_6") (pintype "passive"))
      (node (ref "U1") (pin "1") (pinfunction "EN_1") (pintype "passive"))
      (node (ref "U1") (pin "8") (pinfunction "VIN_8") (pintype "passive"))
    )
    (net (code "52") (name "unconnected-(IC1-3V3-Pad6)") (class "Default")
      (node (ref "IC1") (pin "6") (pinfunction "3V3_6") (pintype "passive+no_connect"))
    )
    (net (code "53") (name "unconnected-(IC1-DM-Pad4)") (class "Default")
      (node (ref "IC1") (pin "4") (pinfunction "DM_4") (pintype "passive+no_connect"))
    )
    (net (code "54") (name "unconnected-(IC1-DP-Pad5)") (class "Default")
      (node (ref "IC1") (pin "5") (pinfunction "DP_5") (pintype "passive+no_connect"))
    )
    (net (code "55") (name "unconnected-(IC1-PA3-Pad1)") (class "Default")
      (node (ref "IC1") (pin "1") (pinfunction "PA3_1") (pintype "passive+no_connect"))
    )
    (net (code "56") (name "unconnected-(IC1-PA4-Pad2)") (class "Default")
      (node (ref "IC1") (pin "2") (pinfunction "PA4_2") (pintype "passive+no_connect"))
    )
    (net (code "57") (name "unconnected-(IC1-PB2-Pad24)") (class "Default")
      (node (ref "IC1") (pin "24") (pinfunction "PB2_24") (pintype "passive"))
    )
    (net (code "58") (name "unconnected-(IC1-PB4-Pad22)") (class "Default")
      (node (ref "IC1") (pin "22") (pinfunction "PB4_22") (pintype "passive+no_connect"))
    )
    (net (code "59") (name "unconnected-(IC1-PB5-Pad21)") (class "Default")
      (node (ref "IC1") (pin "21") (pinfunction "PB5_21") (pintype "passive+no_connect"))
    )
    (net (code "60") (name "unconnected-(IC1-PB6-Pad20)") (class "Default")
      (node (ref "IC1") (pin "20") (pinfunction "PB6_20") (pintype "passive+no_connect"))
    )
    (net (code "61") (name "unconnected-(IC1-PC3-Pad15)") (class "Default")
      (node (ref "IC1") (pin "15") (pinfunction "PC3_15") (pintype "passive+no_connect"))
    )
    (net (code "62") (name "unconnected-(IC1-PC4-Pad16)") (class "Default")
      (node (ref "IC1") (pin "16") (pinfunction "PC4_16") (pintype "passive+no_connect"))
    )
    (net (code "63") (name "unconnected-(IC1-PC5-Pad17)") (class "Default")
      (node (ref "IC1") (pin "17") (pinfunction "PC5_17") (pintype "passive+no_connect"))
    )
    (net (code "64") (name "unconnected-(IC1-PR1-Pad19)") (class "Default")
      (node (ref "IC1") (pin "19") (pinfunction "PR1_19") (pintype "passive+no_connect"))
    )
    (net (code "65") (name "unconnected-(IC1-PR2-Pad18)") (class "Default")
      (node (ref "IC1") (pin "18") (pinfunction "PR2_18") (pintype "passive+no_connect"))
    )
    (net (code "66") (name "unconnected-(IC2-EXTCLK_{slash}PA3-Pad2)") (class "Default")
      (node (ref "IC2") (pin "2") (pinfunction "EXTCLK_/PA3_2") (pintype "passive+no_connect"))
    )
    (net (code "67") (name "unconnected-(IC2-PA6-Pad7)") (class "Default")
      (node (ref "IC2") (pin "7") (pinfunction "PA6_7") (pintype "passive"))
    )
    (net (code "68") (name "unconnected-(IC2-PA7-Pad8)") (class "Default")
      (node (ref "IC2") (pin "8") (pinfunction "PA7_8") (pintype "passive"))
    )
    (net (code "69") (name "unconnected-(IC2-PB6-Pad10)") (class "Default")
      (node (ref "IC2") (pin "10") (pinfunction "PB6_10") (pintype "passive+no_connect"))
    )
    (net (code "70") (name "unconnected-(IC2-PB7-Pad9)") (class "Default")
      (node (ref "IC2") (pin "9") (pinfunction "PB7_9") (pintype "passive+no_connect"))
    )
    (net (code "71") (name "unconnected-(IC2-PC3-Pad20)") (class "Default")
      (node (ref "IC2") (pin "20") (pinfunction "PC3_20") (pintype "passive+no_connect"))
    )
    (net (code "72") (name "unconnected-(IC2-PC4-Pad21)") (class "Default")
      (node (ref "IC2") (pin "21") (pinfunction "PC4_21") (pintype "passive+no_connect"))
    )
    (net (code "73") (name "unconnected-(IC2-PC5-Pad22)") (class "Default")
      (node (ref "IC2") (pin "22") (pinfunction "PC5_22") (pintype "passive+no_connect"))
    )
    (net (code "74") (name "unconnected-(J1-Pad4)") (class "Default")
      (node (ref "J1") (pin "4") (pinfunction "4_4") (pintype "passive+no_connect"))
    )
    (net (code "75") (name "unconnected-(J2-Pad2)") (class "Default")
      (node (ref "J2") (pin "2") (pinfunction "2_2") (pintype "passive+no_connect"))
    )
    (net (code "76") (name "unconnected-(J2-Pad3)") (class "Default")
      (node (ref "J2") (pin "3") (pinfunction "3_3") (pintype "passive+no_connect"))
    )
    (net (code "77") (name "unconnected-(J2-Pad4)") (class "Default")
      (node (ref "J2") (pin "4") (pinfunction "4_4") (pintype "passive+no_connect"))
    )
    (net (code "78") (name "unconnected-(J2-Pad6)") (class "Default")
      (node (ref "J2") (pin "6") (pinfunction "6_6") (pintype "passive+no_connect"))
    )
    (net (code "79") (name "unconnected-(J2-Pad7)") (class "Default")
      (node (ref "J2") (pin "7") (pinfunction "7_7") (pintype "passive+no_connect"))
    )
    (net (code "80") (name "unconnected-(J2-Pad8)") (class "Default")
      (node (ref "J2") (pin "8") (pinfunction "8_8") (pintype "passive+no_connect"))
    )
    (net (code "81") (name "unconnected-(J2-Pad9)") (class "Default")
      (node (ref "J2") (pin "9") (pinfunction "9_9") (pintype "passive+no_connect"))
    )
    (net (code "82") (name "unconnected-(J2-Pad10)") (class "Default")
      (node (ref "J2") (pin "10") (pinfunction "10_10") (pintype "passive+no_connect"))
    )
    (net (code "83") (name "unconnected-(J2-Pad11)") (class "Default")
      (node (ref "J2") (pin "11") (pinfunction "11_11") (pintype "passive+no_connect"))
    )
    (net (code "84") (name "unconnected-(Q2-D@1-Pad1)") (class "Default")
      (node (ref "Q2") (pin "1") (pinfunction "D@1_1") (pintype "passive"))
    )
    (net (code "85") (name "unconnected-(Q2-D@2-Pad2)") (class "Default")
      (node (ref "Q2") (pin "2") (pinfunction "D@2_2") (pintype "passive"))
    )
    (net (code "86") (name "unconnected-(Q2-D@3-Pad5)") (class "Default")
      (node (ref "Q2") (pin "5") (pinfunction "D@3_5") (pintype "passive"))
    )
    (net (code "87") (name "unconnected-(U1-NC-Pad2)") (class "Default")
      (node (ref "U1") (pin "2") (pinfunction "NC_2") (pintype "passive+no_connect"))
    )
    (net (code "88") (name "unconnected-(U1-PG-Pad3)") (class "Default")
      (node (ref "U1") (pin "3") (pinfunction "PG_3") (pintype "passive+no_connect"))
    )
  )
)
